# SCH_Smart_Card_Contactless_Raspberry_Pi_.net
KiCad netlist of a schematic drawn in EasyEDA
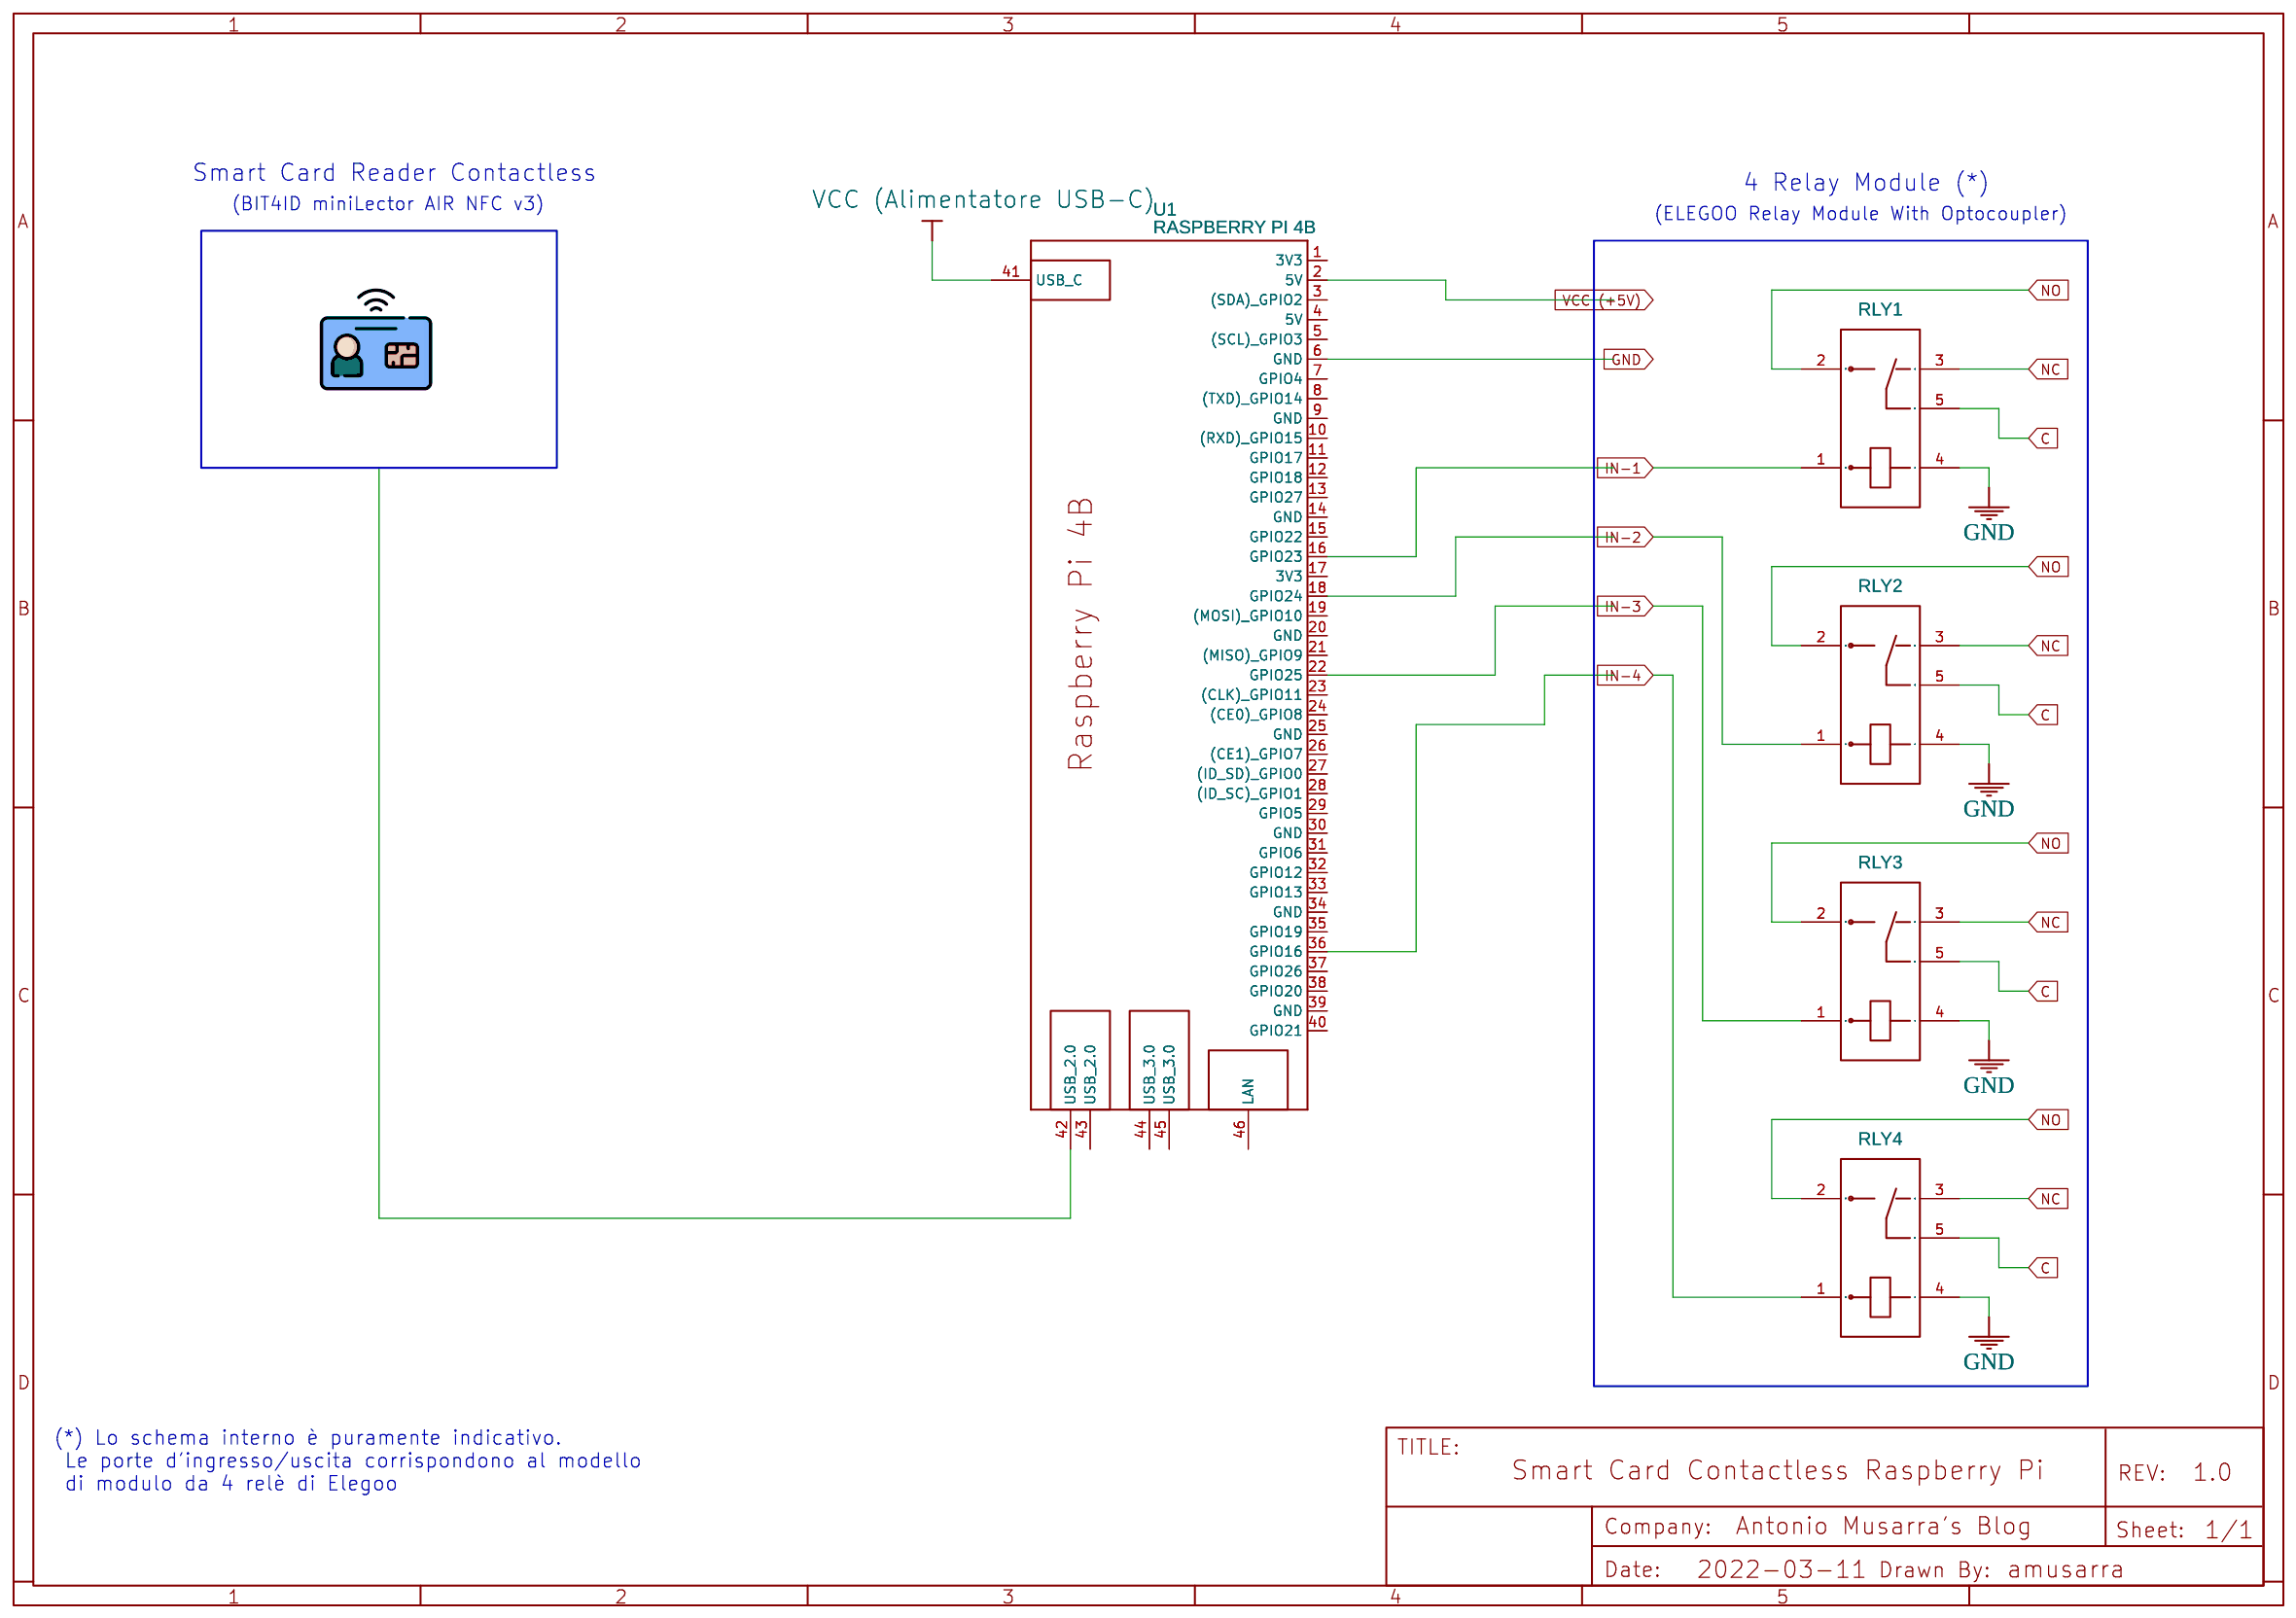
[diagram p0: schematic sheet]

(export (version "E")
  (design (tool "Eeschema 10.0.6"))
  (components
    (comp (ref "RLY1")
      (value "SRD-05VDC-SL-C")
      (fields (field (name "BOM_Supplier Part") "C35449"))
      (libsource (lib "") (part "SRD-05VDC-SL-C"))
    )
    (comp (ref "RLY2")
      (value "SRD-05VDC-SL-C")
      (fields (field (name "BOM_Supplier Part") "C35449"))
      (libsource (lib "") (part "SRD-05VDC-SL-C"))
    )
    (comp (ref "RLY3")
      (value "SRD-05VDC-SL-C")
      (fields (field (name "BOM_Supplier Part") "C35449"))
      (libsource (lib "") (part "SRD-05VDC-SL-C"))
    )
    (comp (ref "RLY4")
      (value "SRD-05VDC-SL-C")
      (fields (field (name "BOM_Supplier Part") "C35449"))
      (libsource (lib "") (part "SRD-05VDC-SL-C"))
    )
    (comp (ref "U1")
      (value "RASPBERRY PI 4B")
      (fields (field (name "BOM_Manufacturer Part") "Raspberry Pi"))
      (libsource (lib "") (part "RASPBERRY PI 4B"))
    )
  )
  (nets
    (net (code "1") (name "C") (class "Default")
      (node (ref "RLY1") (pin "5") (pinfunction "5_5") (pintype "input"))
      (node (ref "RLY2") (pin "5") (pinfunction "5_5") (pintype "input"))
      (node (ref "RLY3") (pin "5") (pinfunction "5_5") (pintype "input"))
      (node (ref "RLY4") (pin "5") (pinfunction "5_5") (pintype "input"))
    )
    (net (code "2") (name "GND") (class "Default")
      (node (ref "RLY1") (pin "4") (pinfunction "4_4") (pintype "input"))
      (node (ref "RLY2") (pin "4") (pinfunction "4_4") (pintype "input"))
      (node (ref "RLY3") (pin "4") (pinfunction "4_4") (pintype "input"))
      (node (ref "RLY4") (pin "4") (pinfunction "4_4") (pintype "input"))
    )
    (net (code "3") (name "IN-1") (class "Default")
      (node (ref "RLY1") (pin "1") (pinfunction "1_1") (pintype "input"))
    )
    (net (code "4") (name "IN-2") (class "Default")
      (node (ref "RLY2") (pin "1") (pinfunction "1_1") (pintype "input"))
    )
    (net (code "5") (name "IN-3") (class "Default")
      (node (ref "RLY3") (pin "1") (pinfunction "1_1") (pintype "input"))
    )
    (net (code "6") (name "IN-4") (class "Default")
      (node (ref "RLY4") (pin "1") (pinfunction "1_1") (pintype "input"))
    )
    (net (code "7") (name "NC") (class "Default")
      (node (ref "RLY1") (pin "3") (pinfunction "3_3") (pintype "input"))
      (node (ref "RLY2") (pin "3") (pinfunction "3_3") (pintype "input"))
      (node (ref "RLY3") (pin "3") (pinfunction "3_3") (pintype "input"))
      (node (ref "RLY4") (pin "3") (pinfunction "3_3") (pintype "input"))
    )
    (net (code "8") (name "NO") (class "Default")
      (node (ref "RLY1") (pin "2") (pinfunction "2_2") (pintype "input"))
      (node (ref "RLY2") (pin "2") (pinfunction "2_2") (pintype "input"))
      (node (ref "RLY3") (pin "2") (pinfunction "2_2") (pintype "input"))
      (node (ref "RLY4") (pin "2") (pinfunction "2_2") (pintype "input"))
    )
    (net (code "10") (name "VCC (Alimentatore USB-C)") (class "Default")
      (node (ref "U1") (pin "41") (pinfunction "USB_C_41") (pintype "unspecified"))
    )
    (net (code "11") (name "unconnected-(U1-(CE0)_GPIO8-Pad24)") (class "Default")
      (node (ref "U1") (pin "24") (pinfunction "(CE0)_GPIO8_24") (pintype "unspecified"))
    )
    (net (code "12") (name "unconnected-(U1-(CE1)_GPIO7-Pad26)") (class "Default")
      (node (ref "U1") (pin "26") (pinfunction "(CE1)_GPIO7_26") (pintype "unspecified"))
    )
    (net (code "13") (name "unconnected-(U1-(CLK)_GPIO11-Pad23)") (class "Default")
      (node (ref "U1") (pin "23") (pinfunction "(CLK)_GPIO11_23") (pintype "unspecified"))
    )
    (net (code "14") (name "unconnected-(U1-(ID_SC)_GPIO1-Pad28)") (class "Default")
      (node (ref "U1") (pin "28") (pinfunction "(ID_SC)_GPIO1_28") (pintype "unspecified"))
    )
    (net (code "15") (name "unconnected-(U1-(ID_SD)_GPIO0-Pad27)") (class "Default")
      (node (ref "U1") (pin "27") (pinfunction "(ID_SD)_GPIO0_27") (pintype "unspecified"))
    )
    (net (code "16") (name "unconnected-(U1-(MISO)_GPIO9-Pad21)") (class "Default")
      (node (ref "U1") (pin "21") (pinfunction "(MISO)_GPIO9_21") (pintype "unspecified"))
    )
    (net (code "17") (name "unconnected-(U1-(MOSI)_GPIO10-Pad19)") (class "Default")
      (node (ref "U1") (pin "19") (pinfunction "(MOSI)_GPIO10_19") (pintype "unspecified"))
    )
    (net (code "18") (name "unconnected-(U1-(RXD)_GPIO15-Pad10)") (class "Default")
      (node (ref "U1") (pin "10") (pinfunction "(RXD)_GPIO15_10") (pintype "unspecified"))
    )
    (net (code "19") (name "unconnected-(U1-(SCL)_GPIO3-Pad5)") (class "Default")
      (node (ref "U1") (pin "5") (pinfunction "(SCL)_GPIO3_5") (pintype "unspecified"))
    )
    (net (code "20") (name "unconnected-(U1-(SDA)_GPIO2-Pad3)") (class "Default")
      (node (ref "U1") (pin "3") (pinfunction "(SDA)_GPIO2_3") (pintype "unspecified"))
    )
    (net (code "21") (name "unconnected-(U1-(TXD)_GPIO14-Pad8)") (class "Default")
      (node (ref "U1") (pin "8") (pinfunction "(TXD)_GPIO14_8") (pintype "unspecified"))
    )
    (net (code "22") (name "unconnected-(U1-3V3-Pad1)") (class "Default")
      (node (ref "U1") (pin "1") (pinfunction "3V3_1") (pintype "unspecified"))
    )
    (net (code "23") (name "unconnected-(U1-3V3-Pad17)") (class "Default")
      (node (ref "U1") (pin "17") (pinfunction "3V3_17") (pintype "unspecified"))
    )
    (net (code "24") (name "unconnected-(U1-5V-Pad2)") (class "Default")
      (node (ref "U1") (pin "2") (pinfunction "5V_2") (pintype "unspecified"))
    )
    (net (code "25") (name "unconnected-(U1-5V-Pad4)") (class "Default")
      (node (ref "U1") (pin "4") (pinfunction "5V_4") (pintype "unspecified"))
    )
    (net (code "26") (name "unconnected-(U1-GND-Pad6)") (class "Default")
      (node (ref "U1") (pin "6") (pinfunction "GND_6") (pintype "unspecified"))
    )
    (net (code "27") (name "unconnected-(U1-GND-Pad9)") (class "Default")
      (node (ref "U1") (pin "9") (pinfunction "GND_9") (pintype "unspecified"))
    )
    (net (code "28") (name "unconnected-(U1-GND-Pad14)") (class "Default")
      (node (ref "U1") (pin "14") (pinfunction "GND_14") (pintype "unspecified"))
    )
    (net (code "29") (name "unconnected-(U1-GND-Pad20)") (class "Default")
      (node (ref "U1") (pin "20") (pinfunction "GND_20") (pintype "unspecified"))
    )
    (net (code "30") (name "unconnected-(U1-GND-Pad25)") (class "Default")
      (node (ref "U1") (pin "25") (pinfunction "GND_25") (pintype "unspecified"))
    )
    (net (code "31") (name "unconnected-(U1-GND-Pad30)") (class "Default")
      (node (ref "U1") (pin "30") (pinfunction "GND_30") (pintype "unspecified"))
    )
    (net (code "32") (name "unconnected-(U1-GND-Pad34)") (class "Default")
      (node (ref "U1") (pin "34") (pinfunction "GND_34") (pintype "unspecified"))
    )
    (net (code "33") (name "unconnected-(U1-GND-Pad39)") (class "Default")
      (node (ref "U1") (pin "39") (pinfunction "GND_39") (pintype "unspecified"))
    )
    (net (code "34") (name "unconnected-(U1-GPIO4-Pad7)") (class "Default")
      (node (ref "U1") (pin "7") (pinfunction "GPIO4_7") (pintype "unspecified"))
    )
    (net (code "35") (name "unconnected-(U1-GPIO5-Pad29)") (class "Default")
      (node (ref "U1") (pin "29") (pinfunction "GPIO5_29") (pintype "unspecified"))
    )
    (net (code "36") (name "unconnected-(U1-GPIO6-Pad31)") (class "Default")
      (node (ref "U1") (pin "31") (pinfunction "GPIO6_31") (pintype "unspecified"))
    )
    (net (code "37") (name "unconnected-(U1-GPIO12-Pad32)") (class "Default")
      (node (ref "U1") (pin "32") (pinfunction "GPIO12_32") (pintype "unspecified"))
    )
    (net (code "38") (name "unconnected-(U1-GPIO13-Pad33)") (class "Default")
      (node (ref "U1") (pin "33") (pinfunction "GPIO13_33") (pintype "unspecified"))
    )
    (net (code "39") (name "unconnected-(U1-GPIO16-Pad36)") (class "Default")
      (node (ref "U1") (pin "36") (pinfunction "GPIO16_36") (pintype "unspecified"))
    )
    (net (code "40") (name "unconnected-(U1-GPIO17-Pad11)") (class "Default")
      (node (ref "U1") (pin "11") (pinfunction "GPIO17_11") (pintype "unspecified"))
    )
    (net (code "41") (name "unconnected-(U1-GPIO18-Pad12)") (class "Default")
      (node (ref "U1") (pin "12") (pinfunction "GPIO18_12") (pintype "unspecified"))
    )
    (net (code "42") (name "unconnected-(U1-GPIO19-Pad35)") (class "Default")
      (node (ref "U1") (pin "35") (pinfunction "GPIO19_35") (pintype "unspecified"))
    )
    (net (code "43") (name "unconnected-(U1-GPIO20-Pad38)") (class "Default")
      (node (ref "U1") (pin "38") (pinfunction "GPIO20_38") (pintype "unspecified"))
    )
    (net (code "44") (name "unconnected-(U1-GPIO21-Pad40)") (class "Default")
      (node (ref "U1") (pin "40") (pinfunction "GPIO21_40") (pintype "unspecified"))
    )
    (net (code "45") (name "unconnected-(U1-GPIO22-Pad15)") (class "Default")
      (node (ref "U1") (pin "15") (pinfunction "GPIO22_15") (pintype "unspecified"))
    )
    (net (code "46") (name "unconnected-(U1-GPIO23-Pad16)") (class "Default")
      (node (ref "U1") (pin "16") (pinfunction "GPIO23_16") (pintype "unspecified"))
    )
    (net (code "47") (name "unconnected-(U1-GPIO24-Pad18)") (class "Default")
      (node (ref "U1") (pin "18") (pinfunction "GPIO24_18") (pintype "unspecified"))
    )
    (net (code "48") (name "unconnected-(U1-GPIO25-Pad22)") (class "Default")
      (node (ref "U1") (pin "22") (pinfunction "GPIO25_22") (pintype "unspecified"))
    )
    (net (code "49") (name "unconnected-(U1-GPIO26-Pad37)") (class "Default")
      (node (ref "U1") (pin "37") (pinfunction "GPIO26_37") (pintype "unspecified"))
    )
    (net (code "50") (name "unconnected-(U1-GPIO27-Pad13)") (class "Default")
      (node (ref "U1") (pin "13") (pinfunction "GPIO27_13") (pintype "unspecified"))
    )
    (net (code "51") (name "unconnected-(U1-LAN-Pad46)") (class "Default")
      (node (ref "U1") (pin "46") (pinfunction "LAN_46") (pintype "unspecified"))
    )
    (net (code "52") (name "unconnected-(U1-USB_2.0-Pad42)") (class "Default")
      (node (ref "U1") (pin "42") (pinfunction "USB_2.0_42") (pintype "unspecified"))
    )
    (net (code "53") (name "unconnected-(U1-USB_2.0-Pad43)") (class "Default")
      (node (ref "U1") (pin "43") (pinfunction "USB_2.0_43") (pintype "unspecified"))
    )
    (net (code "54") (name "unconnected-(U1-USB_3.0-Pad44)") (class "Default")
      (node (ref "U1") (pin "44") (pinfunction "USB_3.0_44") (pintype "unspecified"))
    )
    (net (code "55") (name "unconnected-(U1-USB_3.0-Pad45)") (class "Default")
      (node (ref "U1") (pin "45") (pinfunction "USB_3.0_45") (pintype "unspecified"))
    )
  )
)
